# bmp280_i2c.net
KiCad netlist of a schematic drawn in Altium Designer
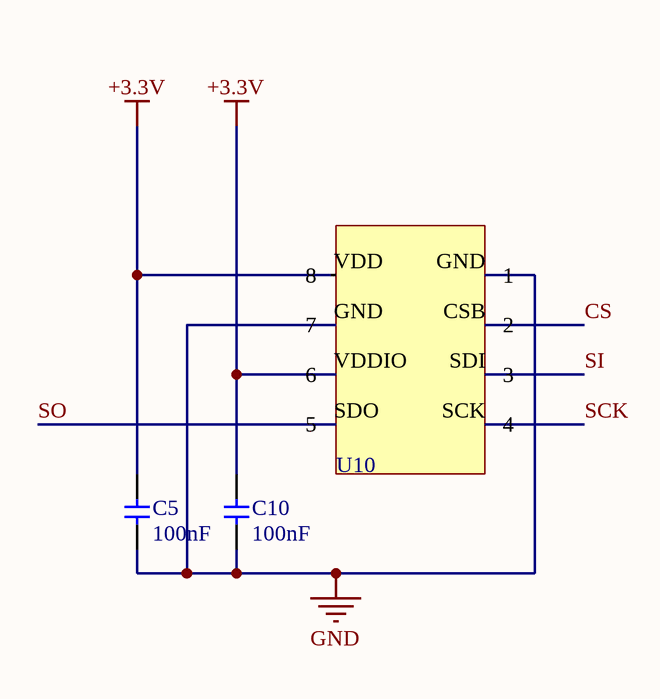
[diagram p0: bmp280_i2c.SchDoc]

(export (version "E")
  (design (tool "Eeschema 10.0.6"))
  (components
    (comp (ref "C5")
      (value "100nF")
      (footprint "0805")
      (description "Generic capacitor")
      (fields (field (name "Comment") "Generic Capacitor"))
      (libsource (lib "PowerCircuit") (part "Capacitor"))
    )
    (comp (ref "C10")
      (value "100nF")
      (footprint "0805")
      (description "Generic capacitor")
      (fields (field (name "Comment") "Generic Capacitor"))
      (libsource (lib "PowerCircuit") (part "Capacitor"))
    )
    (comp (ref "U10")
      (value "BMP280")
      (footprint "bmp280_i2c:bmp280_i2c")
      (libsource (lib "bmp280_i2c") (part "BMP280"))
    )
  )
  (nets
    (net (code "1") (name "+3.3V") (class "Default")
      (node (ref "C10") (pin "1") (pinfunction "1_1") (pintype "passive"))
      (node (ref "C5") (pin "1") (pinfunction "1_1") (pintype "passive"))
      (node (ref "U10") (pin "VDD") (pinfunction "8_VDD") (pintype "passive"))
      (node (ref "U10") (pin "VDDIO") (pinfunction "6_VDDIO") (pintype "passive"))
    )
    (net (code "2") (name "/CS") (class "Default")
      (node (ref "U10") (pin "CSB") (pinfunction "2_CSB") (pintype "passive"))
    )
    (net (code "3") (name "/SCK") (class "Default")
      (node (ref "U10") (pin "SCK") (pinfunction "4_SCK") (pintype "passive"))
    )
    (net (code "4") (name "/SI") (class "Default")
      (node (ref "U10") (pin "SDI") (pinfunction "3_SDI") (pintype "passive"))
    )
    (net (code "5") (name "/SO") (class "Default")
      (node (ref "U10") (pin "SDO") (pinfunction "5_SDO") (pintype "passive"))
    )
    (net (code "6") (name "GND") (class "Default")
      (node (ref "C10") (pin "2") (pinfunction "2_2") (pintype "passive"))
      (node (ref "C5") (pin "2") (pinfunction "2_2") (pintype "passive"))
      (node (ref "U10") (pin "GND") (pinfunction "7_GND") (pintype "passive"))
    )
  )
)
